# CTL_RELAY_SHEET1_CCU_HAS.net
KiCad netlist of a schematic drawn in Altium Designer
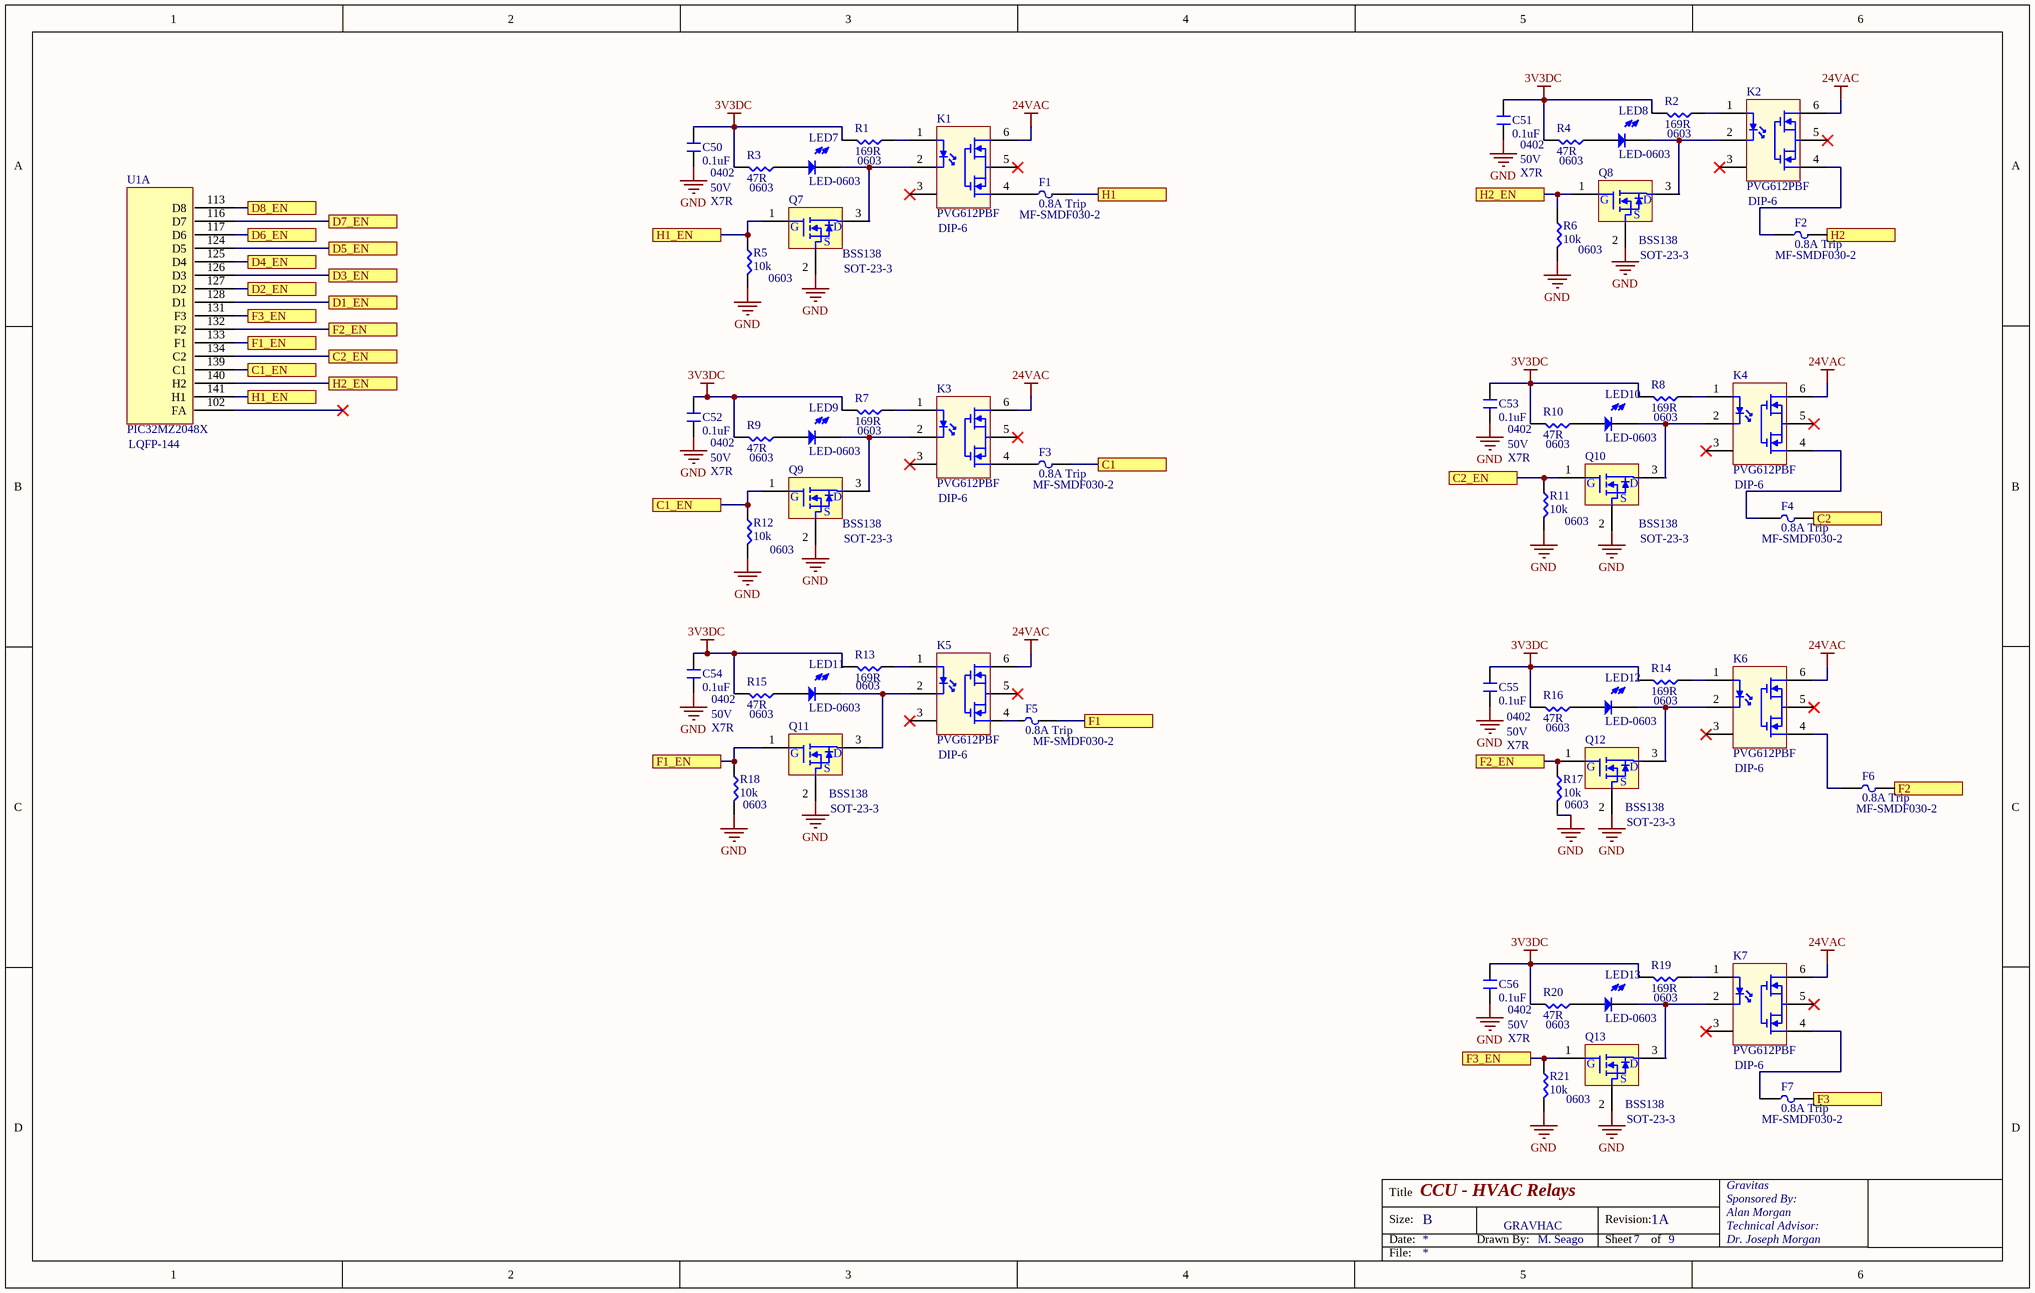
[diagram p0: CTL_RELAY_SHEET1_CCU_HAS.SchDoc]

(export (version "E")
  (design (tool "Eeschema 10.0.6"))
  (components
    (comp (ref "C50")
      (value "0.1uF")
      (footprint "NonPolar-0402")
      (libsource (lib "GravLib") (part "Cap - 0402"))
    )
    (comp (ref "C51")
      (value "0.1uF")
      (footprint "NonPolar-0402")
      (libsource (lib "GravLib") (part "Cap - 0402"))
    )
    (comp (ref "C52")
      (value "0.1uF")
      (footprint "NonPolar-0402")
      (libsource (lib "GravLib") (part "Cap - 0402"))
    )
    (comp (ref "C53")
      (value "0.1uF")
      (footprint "NonPolar-0402")
      (libsource (lib "GravLib") (part "Cap - 0402"))
    )
    (comp (ref "C54")
      (value "0.1uF")
      (footprint "NonPolar-0402")
      (libsource (lib "GravLib") (part "Cap - 0402"))
    )
    (comp (ref "C55")
      (value "0.1uF")
      (footprint "NonPolar-0402")
      (libsource (lib "GravLib") (part "Cap - 0402"))
    )
    (comp (ref "C56")
      (value "0.1uF")
      (footprint "NonPolar-0402")
      (libsource (lib "GravLib") (part "Cap - 0402"))
    )
    (comp (ref "F1")
      (value "0.8A Trip")
      (footprint "Fuse-MF-SMDF030-2")
      (libsource (lib "GravLib") (part "Fuse-MF-SMDF030-2"))
    )
    (comp (ref "F2")
      (value "0.8A Trip")
      (footprint "Fuse-MF-SMDF030-2")
      (libsource (lib "GravLib") (part "Fuse-MF-SMDF030-2"))
    )
    (comp (ref "F3")
      (value "0.8A Trip")
      (footprint "Fuse-MF-SMDF030-2")
      (libsource (lib "GravLib") (part "Fuse-MF-SMDF030-2"))
    )
    (comp (ref "F4")
      (value "0.8A Trip")
      (footprint "Fuse-MF-SMDF030-2")
      (libsource (lib "GravLib") (part "Fuse-MF-SMDF030-2"))
    )
    (comp (ref "F5")
      (value "0.8A Trip")
      (footprint "Fuse-MF-SMDF030-2")
      (libsource (lib "GravLib") (part "Fuse-MF-SMDF030-2"))
    )
    (comp (ref "F6")
      (value "0.8A Trip")
      (footprint "Fuse-MF-SMDF030-2")
      (libsource (lib "GravLib") (part "Fuse-MF-SMDF030-2"))
    )
    (comp (ref "F7")
      (value "0.8A Trip")
      (footprint "Fuse-MF-SMDF030-2")
      (libsource (lib "GravLib") (part "Fuse-MF-SMDF030-2"))
    )
    (comp (ref "K1")
      (value "PVG612PBF")
      (footprint "PVG612PBF")
      (description "PhotoVoltaic Relay")
      (libsource (lib "GravLib") (part "PVG612PBF"))
    )
    (comp (ref "K2")
      (value "PVG612PBF")
      (footprint "PVG612PBF")
      (description "PhotoVoltaic Relay")
      (libsource (lib "GravLib") (part "PVG612PBF"))
    )
    (comp (ref "K3")
      (value "PVG612PBF")
      (footprint "PVG612PBF")
      (description "PhotoVoltaic Relay")
      (libsource (lib "GravLib") (part "PVG612PBF"))
    )
    (comp (ref "K4")
      (value "PVG612PBF")
      (footprint "PVG612PBF")
      (description "PhotoVoltaic Relay")
      (libsource (lib "GravLib") (part "PVG612PBF"))
    )
    (comp (ref "K5")
      (value "PVG612PBF")
      (footprint "PVG612PBF")
      (description "PhotoVoltaic Relay")
      (libsource (lib "GravLib") (part "PVG612PBF"))
    )
    (comp (ref "K6")
      (value "PVG612PBF")
      (footprint "PVG612PBF")
      (description "PhotoVoltaic Relay")
      (libsource (lib "GravLib") (part "PVG612PBF"))
    )
    (comp (ref "K7")
      (value "PVG612PBF")
      (footprint "PVG612PBF")
      (description "PhotoVoltaic Relay")
      (libsource (lib "GravLib") (part "PVG612PBF"))
    )
    (comp (ref "LED7")
      (value "LED-0603")
      (footprint "LED-0603")
      (libsource (lib "GravLib") (part "LED-0603"))
    )
    (comp (ref "LED8")
      (value "LED-0603")
      (footprint "LED-0603")
      (libsource (lib "GravLib") (part "LED-0603"))
    )
    (comp (ref "LED9")
      (value "LED-0603")
      (footprint "LED-0603")
      (libsource (lib "GravLib") (part "LED-0603"))
    )
    (comp (ref "LED10")
      (value "LED-0603")
      (footprint "LED-0603")
      (libsource (lib "GravLib") (part "LED-0603"))
    )
    (comp (ref "LED11")
      (value "LED-0603")
      (footprint "LED-0603")
      (libsource (lib "GravLib") (part "LED-0603"))
    )
    (comp (ref "LED12")
      (value "LED-0603")
      (footprint "LED-0603")
      (libsource (lib "GravLib") (part "LED-0603"))
    )
    (comp (ref "LED13")
      (value "LED-0603")
      (footprint "LED-0603")
      (libsource (lib "GravLib") (part "LED-0603"))
    )
    (comp (ref "Q7") (value "BSS138") (footprint "BSS138-SOT23") (libsource (lib "GravLib") (part "BSS138")))
    (comp (ref "Q8") (value "BSS138") (footprint "BSS138-SOT23") (libsource (lib "GravLib") (part "BSS138")))
    (comp (ref "Q9") (value "BSS138") (footprint "BSS138-SOT23") (libsource (lib "GravLib") (part "BSS138")))
    (comp (ref "Q10") (value "BSS138") (footprint "BSS138-SOT23") (libsource (lib "GravLib") (part "BSS138")))
    (comp (ref "Q11") (value "BSS138") (footprint "BSS138-SOT23") (libsource (lib "GravLib") (part "BSS138")))
    (comp (ref "Q12") (value "BSS138") (footprint "BSS138-SOT23") (libsource (lib "GravLib") (part "BSS138")))
    (comp (ref "Q13") (value "BSS138") (footprint "BSS138-SOT23") (libsource (lib "GravLib") (part "BSS138")))
    (comp (ref "R1")
      (value "169R")
      (footprint "NonPolar-0603")
      (libsource (lib "GravLib") (part "Res - 0603"))
    )
    (comp (ref "R2")
      (value "169R")
      (footprint "NonPolar-0603")
      (libsource (lib "GravLib") (part "Res - 0603"))
    )
    (comp (ref "R3")
      (value "47R")
      (footprint "NonPolar-0603")
      (libsource (lib "GravLib") (part "Res - 0603"))
    )
    (comp (ref "R4")
      (value "47R")
      (footprint "NonPolar-0603")
      (libsource (lib "GravLib") (part "Res - 0603"))
    )
    (comp (ref "R5")
      (value "10k")
      (footprint "NonPolar-0603")
      (libsource (lib "GravLib") (part "Res - 0603"))
    )
    (comp (ref "R6")
      (value "10k")
      (footprint "NonPolar-0603")
      (libsource (lib "GravLib") (part "Res - 0603"))
    )
    (comp (ref "R7")
      (value "169R")
      (footprint "NonPolar-0603")
      (libsource (lib "GravLib") (part "Res - 0603"))
    )
    (comp (ref "R8")
      (value "169R")
      (footprint "NonPolar-0603")
      (libsource (lib "GravLib") (part "Res - 0603"))
    )
    (comp (ref "R9")
      (value "47R")
      (footprint "NonPolar-0603")
      (libsource (lib "GravLib") (part "Res - 0603"))
    )
    (comp (ref "R10")
      (value "47R")
      (footprint "NonPolar-0603")
      (libsource (lib "GravLib") (part "Res - 0603"))
    )
    (comp (ref "R11")
      (value "10k")
      (footprint "NonPolar-0603")
      (libsource (lib "GravLib") (part "Res - 0603"))
    )
    (comp (ref "R12")
      (value "10k")
      (footprint "NonPolar-0603")
      (libsource (lib "GravLib") (part "Res - 0603"))
    )
    (comp (ref "R13")
      (value "169R")
      (footprint "NonPolar-0603")
      (libsource (lib "GravLib") (part "Res - 0603"))
    )
    (comp (ref "R14")
      (value "169R")
      (footprint "NonPolar-0603")
      (libsource (lib "GravLib") (part "Res - 0603"))
    )
    (comp (ref "R15")
      (value "47R")
      (footprint "NonPolar-0603")
      (libsource (lib "GravLib") (part "Res - 0603"))
    )
    (comp (ref "R16")
      (value "47R")
      (footprint "NonPolar-0603")
      (libsource (lib "GravLib") (part "Res - 0603"))
    )
    (comp (ref "R17")
      (value "10k")
      (footprint "NonPolar-0603")
      (libsource (lib "GravLib") (part "Res - 0603"))
    )
    (comp (ref "R18")
      (value "10k")
      (footprint "NonPolar-0603")
      (libsource (lib "GravLib") (part "Res - 0603"))
    )
    (comp (ref "R19")
      (value "169R")
      (footprint "NonPolar-0603")
      (libsource (lib "GravLib") (part "Res - 0603"))
    )
    (comp (ref "R20")
      (value "47R")
      (footprint "NonPolar-0603")
      (libsource (lib "GravLib") (part "Res - 0603"))
    )
    (comp (ref "R21")
      (value "10k")
      (footprint "NonPolar-0603")
      (libsource (lib "GravLib") (part "Res - 0603"))
    )
    (comp (ref "U1")
      (value "PIC32MZ2048X")
      (footprint "BIG_PIC32MZ")
      (libsource (lib "GravLib") (part "PIC32MZ2048X"))
    )
  )
  (nets
    (net (code "1") (name "/C1") (class "Default")
      (node (ref "F3") (pin "2") (pinfunction "2_2") (pintype "passive"))
    )
    (net (code "2") (name "/C1_EN") (class "Default")
      (node (ref "Q9") (pin "1") (pinfunction "G_1") (pintype "passive"))
      (node (ref "R12") (pin "2") (pinfunction "2_2") (pintype "passive"))
      (node (ref "U1") (pin "139") (pinfunction "C1_139") (pintype "passive"))
    )
    (net (code "3") (name "/C2") (class "Default")
      (node (ref "F4") (pin "2") (pinfunction "2_2") (pintype "passive"))
    )
    (net (code "4") (name "/C2_EN") (class "Default")
      (node (ref "Q10") (pin "1") (pinfunction "G_1") (pintype "passive"))
      (node (ref "R11") (pin "2") (pinfunction "2_2") (pintype "passive"))
      (node (ref "U1") (pin "134") (pinfunction "C2_134") (pintype "passive"))
    )
    (net (code "5") (name "/D1_EN") (class "Default")
      (node (ref "U1") (pin "128") (pinfunction "D1_128") (pintype "passive"))
    )
    (net (code "6") (name "/D2_EN") (class "Default")
      (node (ref "U1") (pin "127") (pinfunction "D2_127") (pintype "passive"))
    )
    (net (code "7") (name "/D3_EN") (class "Default")
      (node (ref "U1") (pin "126") (pinfunction "D3_126") (pintype "passive"))
    )
    (net (code "8") (name "/D4_EN") (class "Default")
      (node (ref "U1") (pin "125") (pinfunction "D4_125") (pintype "passive"))
    )
    (net (code "9") (name "/D5_EN") (class "Default")
      (node (ref "U1") (pin "124") (pinfunction "D5_124") (pintype "passive"))
    )
    (net (code "10") (name "/D6_EN") (class "Default")
      (node (ref "U1") (pin "117") (pinfunction "D6_117") (pintype "passive"))
    )
    (net (code "11") (name "/D7_EN") (class "Default")
      (node (ref "U1") (pin "116") (pinfunction "D7_116") (pintype "passive"))
    )
    (net (code "12") (name "/D8_EN") (class "Default")
      (node (ref "U1") (pin "113") (pinfunction "D8_113") (pintype "passive"))
    )
    (net (code "13") (name "/F1") (class "Default")
      (node (ref "F5") (pin "2") (pinfunction "2_2") (pintype "passive"))
    )
    (net (code "14") (name "/F1_EN") (class "Default")
      (node (ref "Q11") (pin "1") (pinfunction "G_1") (pintype "passive"))
      (node (ref "R18") (pin "2") (pinfunction "2_2") (pintype "passive"))
      (node (ref "U1") (pin "133") (pinfunction "F1_133") (pintype "passive"))
    )
    (net (code "15") (name "/F2") (class "Default")
      (node (ref "F6") (pin "2") (pinfunction "2_2") (pintype "passive"))
    )
    (net (code "16") (name "/F2_EN") (class "Default")
      (node (ref "Q12") (pin "1") (pinfunction "G_1") (pintype "passive"))
      (node (ref "R17") (pin "2") (pinfunction "2_2") (pintype "passive"))
      (node (ref "U1") (pin "132") (pinfunction "F2_132") (pintype "passive"))
    )
    (net (code "17") (name "/F3") (class "Default")
      (node (ref "F7") (pin "2") (pinfunction "2_2") (pintype "passive"))
    )
    (net (code "18") (name "/F3_EN") (class "Default")
      (node (ref "Q13") (pin "1") (pinfunction "G_1") (pintype "passive"))
      (node (ref "R21") (pin "2") (pinfunction "2_2") (pintype "passive"))
      (node (ref "U1") (pin "131") (pinfunction "F3_131") (pintype "passive"))
    )
    (net (code "19") (name "/H1") (class "Default")
      (node (ref "F1") (pin "2") (pinfunction "2_2") (pintype "passive"))
    )
    (net (code "20") (name "/H1_EN") (class "Default")
      (node (ref "Q7") (pin "1") (pinfunction "G_1") (pintype "passive"))
      (node (ref "R5") (pin "2") (pinfunction "2_2") (pintype "passive"))
      (node (ref "U1") (pin "141") (pinfunction "H1_141") (pintype "passive"))
    )
    (net (code "21") (name "/H2") (class "Default")
      (node (ref "F2") (pin "2") (pinfunction "2_2") (pintype "passive"))
    )
    (net (code "22") (name "/H2_EN") (class "Default")
      (node (ref "Q8") (pin "1") (pinfunction "G_1") (pintype "passive"))
      (node (ref "R6") (pin "2") (pinfunction "2_2") (pintype "passive"))
      (node (ref "U1") (pin "140") (pinfunction "H2_140") (pintype "passive"))
    )
    (net (code "23") (name "3V3DC") (class "Default")
      (node (ref "C50") (pin "2") (pinfunction "2_2") (pintype "passive"))
      (node (ref "C51") (pin "2") (pinfunction "2_2") (pintype "passive"))
      (node (ref "C52") (pin "2") (pinfunction "2_2") (pintype "passive"))
      (node (ref "C53") (pin "2") (pinfunction "2_2") (pintype "passive"))
      (node (ref "C54") (pin "2") (pinfunction "2_2") (pintype "passive"))
      (node (ref "C55") (pin "2") (pinfunction "2_2") (pintype "passive"))
      (node (ref "C56") (pin "2") (pinfunction "2_2") (pintype "passive"))
      (node (ref "R1") (pin "1") (pinfunction "1_1") (pintype "passive"))
      (node (ref "R10") (pin "1") (pinfunction "1_1") (pintype "passive"))
      (node (ref "R13") (pin "1") (pinfunction "1_1") (pintype "passive"))
      (node (ref "R14") (pin "1") (pinfunction "1_1") (pintype "passive"))
      (node (ref "R15") (pin "1") (pinfunction "1_1") (pintype "passive"))
      (node (ref "R16") (pin "1") (pinfunction "1_1") (pintype "passive"))
      (node (ref "R19") (pin "1") (pinfunction "1_1") (pintype "passive"))
      (node (ref "R2") (pin "1") (pinfunction "1_1") (pintype "passive"))
      (node (ref "R20") (pin "1") (pinfunction "1_1") (pintype "passive"))
      (node (ref "R3") (pin "1") (pinfunction "1_1") (pintype "passive"))
      (node (ref "R4") (pin "1") (pinfunction "1_1") (pintype "passive"))
      (node (ref "R7") (pin "1") (pinfunction "1_1") (pintype "passive"))
      (node (ref "R8") (pin "1") (pinfunction "1_1") (pintype "passive"))
      (node (ref "R9") (pin "1") (pinfunction "1_1") (pintype "passive"))
    )
    (net (code "24") (name "24VAC") (class "Default")
      (node (ref "K1") (pin "6") (pinfunction "13_6") (pintype "passive"))
      (node (ref "K2") (pin "6") (pinfunction "13_6") (pintype "passive"))
      (node (ref "K3") (pin "6") (pinfunction "13_6") (pintype "passive"))
      (node (ref "K4") (pin "6") (pinfunction "13_6") (pintype "passive"))
      (node (ref "K5") (pin "6") (pinfunction "13_6") (pintype "passive"))
      (node (ref "K6") (pin "6") (pinfunction "13_6") (pintype "passive"))
      (node (ref "K7") (pin "6") (pinfunction "13_6") (pintype "passive"))
    )
    (net (code "25") (name "GND") (class "Default")
      (node (ref "C50") (pin "1") (pinfunction "1_1") (pintype "passive"))
      (node (ref "C51") (pin "1") (pinfunction "1_1") (pintype "passive"))
      (node (ref "C52") (pin "1") (pinfunction "1_1") (pintype "passive"))
      (node (ref "C53") (pin "1") (pinfunction "1_1") (pintype "passive"))
      (node (ref "C54") (pin "1") (pinfunction "1_1") (pintype "passive"))
      (node (ref "C55") (pin "1") (pinfunction "1_1") (pintype "passive"))
      (node (ref "C56") (pin "1") (pinfunction "1_1") (pintype "passive"))
      (node (ref "Q10") (pin "2") (pinfunction "S_2") (pintype "passive"))
      (node (ref "Q11") (pin "2") (pinfunction "S_2") (pintype "passive"))
      (node (ref "Q12") (pin "2") (pinfunction "S_2") (pintype "passive"))
      (node (ref "Q13") (pin "2") (pinfunction "S_2") (pintype "passive"))
      (node (ref "Q7") (pin "2") (pinfunction "S_2") (pintype "passive"))
      (node (ref "Q8") (pin "2") (pinfunction "S_2") (pintype "passive"))
      (node (ref "Q9") (pin "2") (pinfunction "S_2") (pintype "passive"))
      (node (ref "R11") (pin "1") (pinfunction "1_1") (pintype "passive"))
      (node (ref "R12") (pin "1") (pinfunction "1_1") (pintype "passive"))
      (node (ref "R17") (pin "1") (pinfunction "1_1") (pintype "passive"))
      (node (ref "R18") (pin "1") (pinfunction "1_1") (pintype "passive"))
      (node (ref "R21") (pin "1") (pinfunction "1_1") (pintype "passive"))
      (node (ref "R5") (pin "1") (pinfunction "1_1") (pintype "passive"))
      (node (ref "R6") (pin "1") (pinfunction "1_1") (pintype "passive"))
    )
    (net (code "26") (name "Net-(K1-15)") (class "Default")
      (node (ref "F1") (pin "1") (pinfunction "1_1") (pintype "passive"))
      (node (ref "K1") (pin "4") (pinfunction "15_4") (pintype "passive"))
    )
    (net (code "27") (name "Net-(K1-16)") (class "Default")
      (node (ref "K1") (pin "1") (pinfunction "16_1") (pintype "passive"))
      (node (ref "R1") (pin "2") (pinfunction "2_2") (pintype "passive"))
    )
    (net (code "28") (name "Net-(K1-17)") (class "Default")
      (node (ref "K1") (pin "2") (pinfunction "17_2") (pintype "passive"))
      (node (ref "LED7") (pin "2") (pinfunction "2_2") (pintype "passive"))
      (node (ref "Q7") (pin "3") (pinfunction "D_3") (pintype "passive"))
    )
    (net (code "29") (name "Net-(K2-15)") (class "Default")
      (node (ref "F2") (pin "1") (pinfunction "1_1") (pintype "passive"))
      (node (ref "K2") (pin "4") (pinfunction "15_4") (pintype "passive"))
    )
    (net (code "30") (name "Net-(K2-16)") (class "Default")
      (node (ref "K2") (pin "1") (pinfunction "16_1") (pintype "passive"))
      (node (ref "R2") (pin "2") (pinfunction "2_2") (pintype "passive"))
    )
    (net (code "31") (name "Net-(K2-17)") (class "Default")
      (node (ref "K2") (pin "2") (pinfunction "17_2") (pintype "passive"))
      (node (ref "LED8") (pin "2") (pinfunction "2_2") (pintype "passive"))
      (node (ref "Q8") (pin "3") (pinfunction "D_3") (pintype "passive"))
    )
    (net (code "32") (name "Net-(K3-15)") (class "Default")
      (node (ref "F3") (pin "1") (pinfunction "1_1") (pintype "passive"))
      (node (ref "K3") (pin "4") (pinfunction "15_4") (pintype "passive"))
    )
    (net (code "33") (name "Net-(K3-16)") (class "Default")
      (node (ref "K3") (pin "1") (pinfunction "16_1") (pintype "passive"))
      (node (ref "R7") (pin "2") (pinfunction "2_2") (pintype "passive"))
    )
    (net (code "34") (name "Net-(K3-17)") (class "Default")
      (node (ref "K3") (pin "2") (pinfunction "17_2") (pintype "passive"))
      (node (ref "LED9") (pin "2") (pinfunction "2_2") (pintype "passive"))
      (node (ref "Q9") (pin "3") (pinfunction "D_3") (pintype "passive"))
    )
    (net (code "35") (name "Net-(K4-15)") (class "Default")
      (node (ref "F4") (pin "1") (pinfunction "1_1") (pintype "passive"))
      (node (ref "K4") (pin "4") (pinfunction "15_4") (pintype "passive"))
    )
    (net (code "36") (name "Net-(K4-16)") (class "Default")
      (node (ref "K4") (pin "1") (pinfunction "16_1") (pintype "passive"))
      (node (ref "R8") (pin "2") (pinfunction "2_2") (pintype "passive"))
    )
    (net (code "37") (name "Net-(K4-17)") (class "Default")
      (node (ref "K4") (pin "2") (pinfunction "17_2") (pintype "passive"))
      (node (ref "LED10") (pin "2") (pinfunction "2_2") (pintype "passive"))
      (node (ref "Q10") (pin "3") (pinfunction "D_3") (pintype "passive"))
    )
    (net (code "38") (name "Net-(K5-15)") (class "Default")
      (node (ref "F5") (pin "1") (pinfunction "1_1") (pintype "passive"))
      (node (ref "K5") (pin "4") (pinfunction "15_4") (pintype "passive"))
    )
    (net (code "39") (name "Net-(K5-16)") (class "Default")
      (node (ref "K5") (pin "1") (pinfunction "16_1") (pintype "passive"))
      (node (ref "R13") (pin "2") (pinfunction "2_2") (pintype "passive"))
    )
    (net (code "40") (name "Net-(K5-17)") (class "Default")
      (node (ref "K5") (pin "2") (pinfunction "17_2") (pintype "passive"))
      (node (ref "LED11") (pin "2") (pinfunction "2_2") (pintype "passive"))
      (node (ref "Q11") (pin "3") (pinfunction "D_3") (pintype "passive"))
    )
    (net (code "41") (name "Net-(K6-15)") (class "Default")
      (node (ref "F6") (pin "1") (pinfunction "1_1") (pintype "passive"))
      (node (ref "K6") (pin "4") (pinfunction "15_4") (pintype "passive"))
    )
    (net (code "42") (name "Net-(K6-16)") (class "Default")
      (node (ref "K6") (pin "1") (pinfunction "16_1") (pintype "passive"))
      (node (ref "R14") (pin "2") (pinfunction "2_2") (pintype "passive"))
    )
    (net (code "43") (name "Net-(K6-17)") (class "Default")
      (node (ref "K6") (pin "2") (pinfunction "17_2") (pintype "passive"))
      (node (ref "LED12") (pin "2") (pinfunction "2_2") (pintype "passive"))
      (node (ref "Q12") (pin "3") (pinfunction "D_3") (pintype "passive"))
    )
    (net (code "44") (name "Net-(K7-15)") (class "Default")
      (node (ref "F7") (pin "1") (pinfunction "1_1") (pintype "passive"))
      (node (ref "K7") (pin "4") (pinfunction "15_4") (pintype "passive"))
    )
    (net (code "45") (name "Net-(K7-16)") (class "Default")
      (node (ref "K7") (pin "1") (pinfunction "16_1") (pintype "passive"))
      (node (ref "R19") (pin "2") (pinfunction "2_2") (pintype "passive"))
    )
    (net (code "46") (name "Net-(K7-17)") (class "Default")
      (node (ref "K7") (pin "2") (pinfunction "17_2") (pintype "passive"))
      (node (ref "LED13") (pin "2") (pinfunction "2_2") (pintype "passive"))
      (node (ref "Q13") (pin "3") (pinfunction "D_3") (pintype "passive"))
    )
    (net (code "47") (name "Net-(LED7-Pad1)") (class "Default")
      (node (ref "LED7") (pin "1") (pinfunction "1_1") (pintype "passive"))
      (node (ref "R3") (pin "2") (pinfunction "2_2") (pintype "passive"))
    )
    (net (code "48") (name "Net-(LED8-Pad1)") (class "Default")
      (node (ref "LED8") (pin "1") (pinfunction "1_1") (pintype "passive"))
      (node (ref "R4") (pin "2") (pinfunction "2_2") (pintype "passive"))
    )
    (net (code "49") (name "Net-(LED9-Pad1)") (class "Default")
      (node (ref "LED9") (pin "1") (pinfunction "1_1") (pintype "passive"))
      (node (ref "R9") (pin "2") (pinfunction "2_2") (pintype "passive"))
    )
    (net (code "50") (name "Net-(LED10-Pad1)") (class "Default")
      (node (ref "LED10") (pin "1") (pinfunction "1_1") (pintype "passive"))
      (node (ref "R10") (pin "2") (pinfunction "2_2") (pintype "passive"))
    )
    (net (code "51") (name "Net-(LED11-Pad1)") (class "Default")
      (node (ref "LED11") (pin "1") (pinfunction "1_1") (pintype "passive"))
      (node (ref "R15") (pin "2") (pinfunction "2_2") (pintype "passive"))
    )
    (net (code "52") (name "Net-(LED12-Pad1)") (class "Default")
      (node (ref "LED12") (pin "1") (pinfunction "1_1") (pintype "passive"))
      (node (ref "R16") (pin "2") (pinfunction "2_2") (pintype "passive"))
    )
    (net (code "53") (name "Net-(LED13-Pad1)") (class "Default")
      (node (ref "LED13") (pin "1") (pinfunction "1_1") (pintype "passive"))
      (node (ref "R20") (pin "2") (pinfunction "2_2") (pintype "passive"))
    )
    (net (code "54") (name "unconnected-(K1-14-Pad5)") (class "Default")
      (node (ref "K1") (pin "5") (pinfunction "14_5") (pintype "passive+no_connect"))
    )
    (net (code "55") (name "unconnected-(K1-18-Pad3)") (class "Default")
      (node (ref "K1") (pin "3") (pinfunction "18_3") (pintype "passive+no_connect"))
    )
    (net (code "56") (name "unconnected-(K2-14-Pad5)") (class "Default")
      (node (ref "K2") (pin "5") (pinfunction "14_5") (pintype "passive+no_connect"))
    )
    (net (code "57") (name "unconnected-(K2-18-Pad3)") (class "Default")
      (node (ref "K2") (pin "3") (pinfunction "18_3") (pintype "passive+no_connect"))
    )
    (net (code "58") (name "unconnected-(K3-14-Pad5)") (class "Default")
      (node (ref "K3") (pin "5") (pinfunction "14_5") (pintype "passive+no_connect"))
    )
    (net (code "59") (name "unconnected-(K3-18-Pad3)") (class "Default")
      (node (ref "K3") (pin "3") (pinfunction "18_3") (pintype "passive+no_connect"))
    )
    (net (code "60") (name "unconnected-(K4-14-Pad5)") (class "Default")
      (node (ref "K4") (pin "5") (pinfunction "14_5") (pintype "passive+no_connect"))
    )
    (net (code "61") (name "unconnected-(K4-18-Pad3)") (class "Default")
      (node (ref "K4") (pin "3") (pinfunction "18_3") (pintype "passive+no_connect"))
    )
    (net (code "62") (name "unconnected-(K5-14-Pad5)") (class "Default")
      (node (ref "K5") (pin "5") (pinfunction "14_5") (pintype "passive+no_connect"))
    )
    (net (code "63") (name "unconnected-(K5-18-Pad3)") (class "Default")
      (node (ref "K5") (pin "3") (pinfunction "18_3") (pintype "passive+no_connect"))
    )
    (net (code "64") (name "unconnected-(K6-14-Pad5)") (class "Default")
      (node (ref "K6") (pin "5") (pinfunction "14_5") (pintype "passive+no_connect"))
    )
    (net (code "65") (name "unconnected-(K6-18-Pad3)") (class "Default")
      (node (ref "K6") (pin "3") (pinfunction "18_3") (pintype "passive+no_connect"))
    )
    (net (code "66") (name "unconnected-(K7-14-Pad5)") (class "Default")
      (node (ref "K7") (pin "5") (pinfunction "14_5") (pintype "passive+no_connect"))
    )
    (net (code "67") (name "unconnected-(K7-18-Pad3)") (class "Default")
      (node (ref "K7") (pin "3") (pinfunction "18_3") (pintype "passive+no_connect"))
    )
    (net (code "68") (name "unconnected-(U1A-FA-Pad102)") (class "Default")
      (node (ref "U1") (pin "102") (pinfunction "FA_102") (pintype "passive+no_connect"))
    )
  )
)
